# shield_mega2.net
KiCad netlist of a schematic drawn in EAGLE
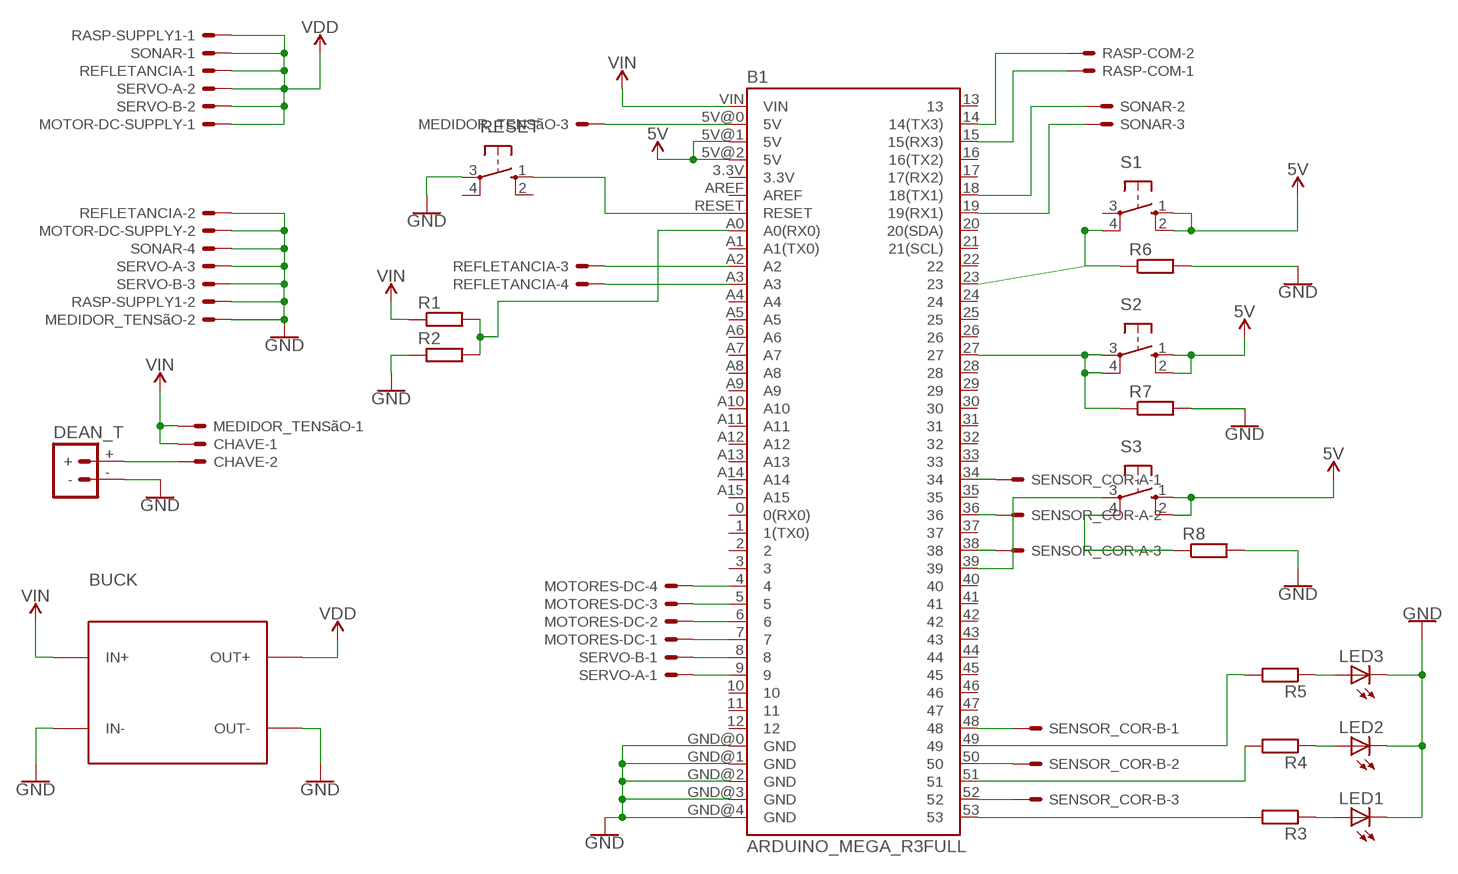
[diagram p0: schematic, sheet 1]

(export (version "E")
  (design (tool "Eeschema 10.0.6"))
  (components
    (comp (ref "B1")
      (value "ARDUINO_MEGA_R3FULL")
      (footprint "eagle-import:ARDUINO_MEGA")
      (libsource (lib "eagle-import") (part "ARDUINO_MEGA_R3FULL"))
    )
    (comp (ref "BUCK")
      (value "DC-DC-STEP-DOWN-LM2596")
      (footprint "eagle-import:DC-DC-STEP-DOWN-LM2596")
      (libsource (lib "eagle-import") (part "DC-DC-STEP-DOWN-LM2596"))
    )
    (comp (ref "CHAVE")
      (value "22-23-2021")
      (footprint "eagle-import:22-23-2021")
      (fields (field (name "MF") "MOLEX"))
      (libsource (lib "eagle-import") (part "22-23-2021"))
    )
    (comp (ref "DEAN_T")
      (value "BATTERY_CONN_DEANS")
      (footprint "eagle-import:DEANS")
      (libsource (lib "eagle-import") (part "BATTERY_CONN_DEANS"))
    )
    (comp (ref "LED1")
      (value "LED5MM")
      (footprint "eagle-import:LED5MM")
      (libsource (lib "eagle-import") (part "LED5MM"))
    )
    (comp (ref "LED2")
      (value "LED5MM")
      (footprint "eagle-import:LED5MM")
      (libsource (lib "eagle-import") (part "LED5MM"))
    )
    (comp (ref "LED3")
      (value "LED5MM")
      (footprint "eagle-import:LED5MM")
      (libsource (lib "eagle-import") (part "LED5MM"))
    )
    (comp (ref "MEDIDOR_TENSãO")
      (value "22-23-2031")
      (footprint "eagle-import:22-23-2031")
      (fields (field (name "MF") "MOLEX"))
      (libsource (lib "eagle-import") (part "22-23-2031"))
    )
    (comp (ref "MOTOR-DC-SUPPLY")
      (value "22-23-2021")
      (footprint "eagle-import:22-23-2021")
      (fields (field (name "MF") "MOLEX"))
      (libsource (lib "eagle-import") (part "22-23-2021"))
    )
    (comp (ref "MOTORES-DC")
      (value "22-23-2041")
      (footprint "eagle-import:22-23-2041")
      (fields (field (name "MF") "MOLEX"))
      (libsource (lib "eagle-import") (part "22-23-2041"))
    )
    (comp (ref "R1")
      (value "R-EU_0207/12")
      (footprint "eagle-import:0207_12")
      (libsource (lib "eagle-import") (part "R-EU_0207/12"))
    )
    (comp (ref "R2")
      (value "R-EU_0207/12")
      (footprint "eagle-import:0207_12")
      (libsource (lib "eagle-import") (part "R-EU_0207/12"))
    )
    (comp (ref "R3")
      (value "R-EU_0207/7")
      (footprint "eagle-import:0207_7")
      (libsource (lib "eagle-import") (part "R-EU_0207/7"))
    )
    (comp (ref "R4")
      (value "R-EU_0207/7")
      (footprint "eagle-import:0207_7")
      (libsource (lib "eagle-import") (part "R-EU_0207/7"))
    )
    (comp (ref "R5")
      (value "R-EU_0207/7")
      (footprint "eagle-import:0207_7")
      (libsource (lib "eagle-import") (part "R-EU_0207/7"))
    )
    (comp (ref "R6")
      (value "R-EU_0204/7")
      (footprint "eagle-import:0204_7")
      (libsource (lib "eagle-import") (part "R-EU_0204/7"))
    )
    (comp (ref "R7")
      (value "R-EU_0204/7")
      (footprint "eagle-import:0204_7")
      (libsource (lib "eagle-import") (part "R-EU_0204/7"))
    )
    (comp (ref "R8")
      (value "R-EU_0204/7")
      (footprint "eagle-import:0204_7")
      (libsource (lib "eagle-import") (part "R-EU_0204/7"))
    )
    (comp (ref "RASP-COM")
      (value "22-23-2021")
      (footprint "eagle-import:22-23-2021")
      (fields (field (name "MF") "MOLEX"))
      (libsource (lib "eagle-import") (part "22-23-2021"))
    )
    (comp (ref "RASP-SUPPLY1")
      (value "22-23-2021")
      (footprint "eagle-import:22-23-2021")
      (fields (field (name "MF") "MOLEX"))
      (libsource (lib "eagle-import") (part "22-23-2021"))
    )
    (comp (ref "REFLETANCIA")
      (value "22-23-2041")
      (footprint "eagle-import:22-23-2041")
      (fields (field (name "MF") "MOLEX"))
      (libsource (lib "eagle-import") (part "22-23-2041"))
    )
    (comp (ref "RESET")
      (value "10-XX")
      (footprint "eagle-import:B3F-10XX")
      (fields (field (name "MPN") "B3F-1000"))
      (libsource (lib "eagle-import") (part "10-XX"))
    )
    (comp (ref "S1")
      (value "10-XX")
      (footprint "eagle-import:B3F-10XX")
      (fields (field (name "MPN") "B3F-1000"))
      (libsource (lib "eagle-import") (part "10-XX"))
    )
    (comp (ref "S2")
      (value "10-XX")
      (footprint "eagle-import:B3F-10XX")
      (fields (field (name "MPN") "B3F-1000"))
      (libsource (lib "eagle-import") (part "10-XX"))
    )
    (comp (ref "S3")
      (value "10-XX")
      (footprint "eagle-import:B3F-10XX")
      (fields (field (name "MPN") "B3F-1000"))
      (libsource (lib "eagle-import") (part "10-XX"))
    )
    (comp (ref "SENSOR_COR-A")
      (value "22-23-2031")
      (footprint "eagle-import:22-23-2031")
      (fields (field (name "MF") "MOLEX"))
      (libsource (lib "eagle-import") (part "22-23-2031"))
    )
    (comp (ref "SENSOR_COR-B")
      (value "22-23-2031")
      (footprint "eagle-import:22-23-2031")
      (fields (field (name "MF") "MOLEX"))
      (libsource (lib "eagle-import") (part "22-23-2031"))
    )
    (comp (ref "SERVO-A")
      (value "22-23-2031")
      (footprint "eagle-import:22-23-2031")
      (fields (field (name "MF") "MOLEX"))
      (libsource (lib "eagle-import") (part "22-23-2031"))
    )
    (comp (ref "SERVO-B")
      (value "22-23-2031")
      (footprint "eagle-import:22-23-2031")
      (fields (field (name "MF") "MOLEX"))
      (libsource (lib "eagle-import") (part "22-23-2031"))
    )
    (comp (ref "SONAR")
      (value "22-23-2041")
      (footprint "eagle-import:22-23-2041")
      (fields (field (name "MF") "MOLEX"))
      (libsource (lib "eagle-import") (part "22-23-2041"))
    )
  )
  (nets
    (net (code "1") (name "5V") (class "Default")
      (node (ref "B1") (pin "5V@1") (pinfunction "5V_5V@1") (pintype "bidirectional"))
      (node (ref "B1") (pin "5V@2") (pinfunction "5V_5V@2") (pintype "bidirectional"))
      (node (ref "S1") (pin "1") (pinfunction "S_1") (pintype "passive"))
      (node (ref "S1") (pin "2") (pinfunction "S1_2") (pintype "passive"))
      (node (ref "S2") (pin "1") (pinfunction "S_1") (pintype "passive"))
      (node (ref "S2") (pin "2") (pinfunction "S1_2") (pintype "passive"))
      (node (ref "S3") (pin "1") (pinfunction "S_1") (pintype "passive"))
      (node (ref "S3") (pin "2") (pinfunction "S1_2") (pintype "passive"))
    )
    (net (code "2") (name "GND") (class "Default")
      (node (ref "B1") (pin "GND@0") (pinfunction "GND_GND@0") (pintype "bidirectional"))
      (node (ref "B1") (pin "GND@1") (pinfunction "GND_GND@1") (pintype "bidirectional"))
      (node (ref "B1") (pin "GND@2") (pinfunction "GND_GND@2") (pintype "bidirectional"))
      (node (ref "B1") (pin "GND@3") (pinfunction "GND_GND@3") (pintype "bidirectional"))
      (node (ref "B1") (pin "GND@4") (pinfunction "GND_GND@4") (pintype "bidirectional"))
      (node (ref "BUCK") (pin "IN-") (pinfunction "IN-_IN-") (pintype "bidirectional"))
      (node (ref "BUCK") (pin "OUT-") (pinfunction "OUT-_OUT-") (pintype "bidirectional"))
      (node (ref "DEAN_T") (pin "-") (pinfunction "-_-") (pintype "passive"))
      (node (ref "LED1") (pin "K") (pinfunction "C_K") (pintype "passive"))
      (node (ref "LED2") (pin "K") (pinfunction "C_K") (pintype "passive"))
      (node (ref "LED3") (pin "K") (pinfunction "C_K") (pintype "passive"))
      (node (ref "MEDIDOR_TENSãO") (pin "2") (pinfunction "S_2") (pintype "passive"))
      (node (ref "MOTOR-DC-SUPPLY") (pin "2") (pinfunction "S_2") (pintype "passive"))
      (node (ref "R2") (pin "1") (pinfunction "1_1") (pintype "passive"))
      (node (ref "R6") (pin "2") (pinfunction "2_2") (pintype "passive"))
      (node (ref "R7") (pin "2") (pinfunction "2_2") (pintype "passive"))
      (node (ref "R8") (pin "2") (pinfunction "2_2") (pintype "passive"))
      (node (ref "RASP-SUPPLY1") (pin "2") (pinfunction "S_2") (pintype "passive"))
      (node (ref "REFLETANCIA") (pin "2") (pinfunction "S_2") (pintype "passive"))
      (node (ref "RESET") (pin "3") (pinfunction "P_3") (pintype "passive"))
      (node (ref "SERVO-A") (pin "3") (pinfunction "S_3") (pintype "passive"))
      (node (ref "SERVO-B") (pin "3") (pinfunction "S_3") (pintype "passive"))
      (node (ref "SONAR") (pin "4") (pinfunction "S_4") (pintype "passive"))
    )
    (net (code "3") (name "Net-(B1-14(TX3))") (class "Default")
      (node (ref "B1") (pin "14") (pinfunction "14(TX3)_14") (pintype "bidirectional"))
      (node (ref "RASP-COM") (pin "2") (pinfunction "S_2") (pintype "passive"))
    )
    (net (code "4") (name "Net-(B1-15(RX3))") (class "Default")
      (node (ref "B1") (pin "15") (pinfunction "15(RX3)_15") (pintype "bidirectional"))
      (node (ref "RASP-COM") (pin "1") (pinfunction "S_1") (pintype "passive"))
    )
    (net (code "5") (name "Net-(B1-18(TX1))") (class "Default")
      (node (ref "B1") (pin "18") (pinfunction "18(TX1)_18") (pintype "bidirectional"))
      (node (ref "SONAR") (pin "2") (pinfunction "S_2") (pintype "passive"))
    )
    (net (code "6") (name "Net-(B1-19(RX1))") (class "Default")
      (node (ref "B1") (pin "19") (pinfunction "19(RX1)_19") (pintype "bidirectional"))
      (node (ref "SONAR") (pin "3") (pinfunction "S_3") (pintype "passive"))
    )
    (net (code "7") (name "Net-(B1-A0(RX0))") (class "Default")
      (node (ref "B1") (pin "A0") (pinfunction "A0(RX0)_A0") (pintype "bidirectional"))
      (node (ref "R1") (pin "2") (pinfunction "2_2") (pintype "passive"))
      (node (ref "R2") (pin "2") (pinfunction "2_2") (pintype "passive"))
    )
    (net (code "8") (name "Net-(B1-Pad49)") (class "Default")
      (node (ref "B1") (pin "49") (pinfunction "49_49") (pintype "bidirectional"))
      (node (ref "R5") (pin "2") (pinfunction "2_2") (pintype "passive"))
    )
    (net (code "9") (name "Net-(B1-Pad51)") (class "Default")
      (node (ref "B1") (pin "51") (pinfunction "51_51") (pintype "bidirectional"))
      (node (ref "R4") (pin "2") (pinfunction "2_2") (pintype "passive"))
    )
    (net (code "10") (name "Net-(B1-Pad53)") (class "Default")
      (node (ref "B1") (pin "53") (pinfunction "53_53") (pintype "bidirectional"))
      (node (ref "R3") (pin "2") (pinfunction "2_2") (pintype "passive"))
    )
    (net (code "11") (name "Net-(CHAVEB-S)") (class "Default")
      (node (ref "CHAVE") (pin "2") (pinfunction "S_2") (pintype "passive"))
      (node (ref "DEAN_T") (pin "+") (pinfunction "+_+") (pintype "passive"))
    )
    (net (code "12") (name "Net-(LED1-PadA)") (class "Default")
      (node (ref "LED1") (pin "A") (pinfunction "A_A") (pintype "passive"))
      (node (ref "R3") (pin "1") (pinfunction "1_1") (pintype "passive"))
    )
    (net (code "13") (name "Net-(LED2-PadA)") (class "Default")
      (node (ref "LED2") (pin "A") (pinfunction "A_A") (pintype "passive"))
      (node (ref "R4") (pin "1") (pinfunction "1_1") (pintype "passive"))
    )
    (net (code "14") (name "Net-(LED3-PadA)") (class "Default")
      (node (ref "LED3") (pin "A") (pinfunction "A_A") (pintype "passive"))
      (node (ref "R5") (pin "1") (pinfunction "1_1") (pintype "passive"))
    )
    (net (code "15") (name "Net-(MEDIDOR_TENSãOC-S)") (class "Default")
      (node (ref "B1") (pin "5V@0") (pinfunction "5V_5V@0") (pintype "bidirectional"))
      (node (ref "MEDIDOR_TENSãO") (pin "3") (pinfunction "S_3") (pintype "passive"))
    )
    (net (code "16") (name "Net-(MOTORES-DCA-S)") (class "Default")
      (node (ref "B1") (pin "7") (pinfunction "7_7") (pintype "bidirectional"))
      (node (ref "MOTORES-DC") (pin "1") (pinfunction "S_1") (pintype "passive"))
    )
    (net (code "17") (name "Net-(MOTORES-DCB-S)") (class "Default")
      (node (ref "B1") (pin "6") (pinfunction "6_6") (pintype "bidirectional"))
      (node (ref "MOTORES-DC") (pin "2") (pinfunction "S_2") (pintype "passive"))
    )
    (net (code "18") (name "Net-(MOTORES-DCC-S)") (class "Default")
      (node (ref "B1") (pin "5") (pinfunction "5_5") (pintype "bidirectional"))
      (node (ref "MOTORES-DC") (pin "3") (pinfunction "S_3") (pintype "passive"))
    )
    (net (code "19") (name "Net-(MOTORES-DCD-S)") (class "Default")
      (node (ref "B1") (pin "4") (pinfunction "4_4") (pintype "bidirectional"))
      (node (ref "MOTORES-DC") (pin "4") (pinfunction "S_4") (pintype "passive"))
    )
    (net (code "20") (name "Net-(REFLETANCIAC-S)") (class "Default")
      (node (ref "B1") (pin "A2") (pinfunction "A2_A2") (pintype "bidirectional"))
      (node (ref "REFLETANCIA") (pin "3") (pinfunction "S_3") (pintype "passive"))
    )
    (net (code "21") (name "Net-(REFLETANCIAD-S)") (class "Default")
      (node (ref "B1") (pin "A3") (pinfunction "A3_A3") (pintype "bidirectional"))
      (node (ref "REFLETANCIA") (pin "4") (pinfunction "S_4") (pintype "passive"))
    )
    (net (code "22") (name "Net-(RESET-S)") (class "Default")
      (node (ref "B1") (pin "RESET") (pinfunction "RESET_RESET") (pintype "bidirectional"))
      (node (ref "RESET") (pin "1") (pinfunction "S_1") (pintype "passive"))
    )
    (net (code "23") (name "Net-(S1-P1)") (class "Default")
      (node (ref "B1") (pin "23") (pinfunction "23_23") (pintype "bidirectional"))
      (node (ref "R6") (pin "1") (pinfunction "1_1") (pintype "passive"))
      (node (ref "S1") (pin "4") (pinfunction "P1_4") (pintype "passive"))
    )
    (net (code "24") (name "Net-(S2-P)") (class "Default")
      (node (ref "B1") (pin "27") (pinfunction "27_27") (pintype "bidirectional"))
      (node (ref "R7") (pin "1") (pinfunction "1_1") (pintype "passive"))
      (node (ref "S2") (pin "3") (pinfunction "P_3") (pintype "passive"))
      (node (ref "S2") (pin "4") (pinfunction "P1_4") (pintype "passive"))
    )
    (net (code "25") (name "Net-(S3-P)") (class "Default")
      (node (ref "B1") (pin "39") (pinfunction "39_39") (pintype "bidirectional"))
      (node (ref "S3") (pin "3") (pinfunction "P_3") (pintype "passive"))
    )
    (net (code "26") (name "Net-(S3-P1)") (class "Default")
      (node (ref "R8") (pin "1") (pinfunction "1_1") (pintype "passive"))
      (node (ref "S3") (pin "4") (pinfunction "P1_4") (pintype "passive"))
    )
    (net (code "27") (name "Net-(SENSOR_COR-AA-S)") (class "Default")
      (node (ref "B1") (pin "34") (pinfunction "34_34") (pintype "bidirectional"))
      (node (ref "SENSOR_COR-A") (pin "1") (pinfunction "S_1") (pintype "passive"))
    )
    (net (code "28") (name "Net-(SENSOR_COR-AB-S)") (class "Default")
      (node (ref "B1") (pin "36") (pinfunction "36_36") (pintype "bidirectional"))
      (node (ref "SENSOR_COR-A") (pin "2") (pinfunction "S_2") (pintype "passive"))
    )
    (net (code "29") (name "Net-(SENSOR_COR-AC-S)") (class "Default")
      (node (ref "B1") (pin "38") (pinfunction "38_38") (pintype "bidirectional"))
      (node (ref "SENSOR_COR-A") (pin "3") (pinfunction "S_3") (pintype "passive"))
    )
    (net (code "30") (name "Net-(SENSOR_COR-BA-S)") (class "Default")
      (node (ref "B1") (pin "48") (pinfunction "48_48") (pintype "bidirectional"))
      (node (ref "SENSOR_COR-B") (pin "1") (pinfunction "S_1") (pintype "passive"))
    )
    (net (code "31") (name "Net-(SENSOR_COR-BB-S)") (class "Default")
      (node (ref "B1") (pin "50") (pinfunction "50_50") (pintype "bidirectional"))
      (node (ref "SENSOR_COR-B") (pin "2") (pinfunction "S_2") (pintype "passive"))
    )
    (net (code "32") (name "Net-(SENSOR_COR-BC-S)") (class "Default")
      (node (ref "B1") (pin "52") (pinfunction "52_52") (pintype "bidirectional"))
      (node (ref "SENSOR_COR-B") (pin "3") (pinfunction "S_3") (pintype "passive"))
    )
    (net (code "33") (name "Net-(SERVO-AA-S)") (class "Default")
      (node (ref "B1") (pin "9") (pinfunction "9_9") (pintype "bidirectional"))
      (node (ref "SERVO-A") (pin "1") (pinfunction "S_1") (pintype "passive"))
    )
    (net (code "34") (name "Net-(SERVO-BA-S)") (class "Default")
      (node (ref "B1") (pin "8") (pinfunction "8_8") (pintype "bidirectional"))
      (node (ref "SERVO-B") (pin "1") (pinfunction "S_1") (pintype "passive"))
    )
    (net (code "35") (name "VDD") (class "Default")
      (node (ref "BUCK") (pin "OUT+") (pinfunction "OUT+_OUT+") (pintype "bidirectional"))
      (node (ref "MOTOR-DC-SUPPLY") (pin "1") (pinfunction "S_1") (pintype "passive"))
      (node (ref "RASP-SUPPLY1") (pin "1") (pinfunction "S_1") (pintype "passive"))
      (node (ref "REFLETANCIA") (pin "1") (pinfunction "S_1") (pintype "passive"))
      (node (ref "SERVO-A") (pin "2") (pinfunction "S_2") (pintype "passive"))
      (node (ref "SERVO-B") (pin "2") (pinfunction "S_2") (pintype "passive"))
      (node (ref "SONAR") (pin "1") (pinfunction "S_1") (pintype "passive"))
    )
    (net (code "36") (name "VIN") (class "Default")
      (node (ref "B1") (pin "VIN") (pinfunction "VIN_VIN") (pintype "bidirectional"))
      (node (ref "BUCK") (pin "IN+") (pinfunction "IN+_IN+") (pintype "bidirectional"))
      (node (ref "CHAVE") (pin "1") (pinfunction "S_1") (pintype "passive"))
      (node (ref "MEDIDOR_TENSãO") (pin "1") (pinfunction "S_1") (pintype "passive"))
      (node (ref "R1") (pin "1") (pinfunction "1_1") (pintype "passive"))
    )
    (net (code "37") (name "unconnected-(B1-0(RX0)-Pad0)") (class "Default")
      (node (ref "B1") (pin "0") (pinfunction "0(RX0)_0") (pintype "bidirectional"))
    )
    (net (code "38") (name "unconnected-(B1-1(TX0)-Pad1)") (class "Default")
      (node (ref "B1") (pin "1") (pinfunction "1(TX0)_1") (pintype "bidirectional"))
    )
    (net (code "39") (name "unconnected-(B1-16(TX2)-Pad16)") (class "Default")
      (node (ref "B1") (pin "16") (pinfunction "16(TX2)_16") (pintype "bidirectional"))
    )
    (net (code "40") (name "unconnected-(B1-17(RX2)-Pad17)") (class "Default")
      (node (ref "B1") (pin "17") (pinfunction "17(RX2)_17") (pintype "bidirectional"))
    )
    (net (code "41") (name "unconnected-(B1-20(SDA)-Pad20)") (class "Default")
      (node (ref "B1") (pin "20") (pinfunction "20(SDA)_20") (pintype "bidirectional"))
    )
    (net (code "42") (name "unconnected-(B1-21(SCL)-Pad21)") (class "Default")
      (node (ref "B1") (pin "21") (pinfunction "21(SCL)_21") (pintype "bidirectional"))
    )
    (net (code "43") (name "unconnected-(B1-A1(TX0)-PadA1)") (class "Default")
      (node (ref "B1") (pin "A1") (pinfunction "A1(TX0)_A1") (pintype "bidirectional"))
    )
    (net (code "44") (name "unconnected-(B1-Pad2)") (class "Default")
      (node (ref "B1") (pin "2") (pinfunction "2_2") (pintype "bidirectional"))
    )
    (net (code "45") (name "unconnected-(B1-Pad3)") (class "Default")
      (node (ref "B1") (pin "3") (pinfunction "3_3") (pintype "bidirectional"))
    )
    (net (code "46") (name "unconnected-(B1-Pad3.3V)") (class "Default")
      (node (ref "B1") (pin "3.3V") (pinfunction "3.3V_3.3V") (pintype "bidirectional"))
    )
    (net (code "47") (name "unconnected-(B1-Pad10)") (class "Default")
      (node (ref "B1") (pin "10") (pinfunction "10_10") (pintype "bidirectional"))
    )
    (net (code "48") (name "unconnected-(B1-Pad11)") (class "Default")
      (node (ref "B1") (pin "11") (pinfunction "11_11") (pintype "bidirectional"))
    )
    (net (code "49") (name "unconnected-(B1-Pad12)") (class "Default")
      (node (ref "B1") (pin "12") (pinfunction "12_12") (pintype "bidirectional"))
    )
    (net (code "50") (name "unconnected-(B1-Pad13)") (class "Default")
      (node (ref "B1") (pin "13") (pinfunction "13_13") (pintype "bidirectional"))
    )
    (net (code "51") (name "unconnected-(B1-Pad22)") (class "Default")
      (node (ref "B1") (pin "22") (pinfunction "22_22") (pintype "bidirectional"))
    )
    (net (code "52") (name "unconnected-(B1-Pad24)") (class "Default")
      (node (ref "B1") (pin "24") (pinfunction "24_24") (pintype "bidirectional"))
    )
    (net (code "53") (name "unconnected-(B1-Pad25)") (class "Default")
      (node (ref "B1") (pin "25") (pinfunction "25_25") (pintype "bidirectional"))
    )
    (net (code "54") (name "unconnected-(B1-Pad26)") (class "Default")
      (node (ref "B1") (pin "26") (pinfunction "26_26") (pintype "bidirectional"))
    )
    (net (code "55") (name "unconnected-(B1-Pad28)") (class "Default")
      (node (ref "B1") (pin "28") (pinfunction "28_28") (pintype "bidirectional"))
    )
    (net (code "56") (name "unconnected-(B1-Pad29)") (class "Default")
      (node (ref "B1") (pin "29") (pinfunction "29_29") (pintype "bidirectional"))
    )
    (net (code "57") (name "unconnected-(B1-Pad30)") (class "Default")
      (node (ref "B1") (pin "30") (pinfunction "30_30") (pintype "bidirectional"))
    )
    (net (code "58") (name "unconnected-(B1-Pad31)") (class "Default")
      (node (ref "B1") (pin "31") (pinfunction "31_31") (pintype "bidirectional"))
    )
    (net (code "59") (name "unconnected-(B1-Pad32)") (class "Default")
      (node (ref "B1") (pin "32") (pinfunction "32_32") (pintype "bidirectional"))
    )
    (net (code "60") (name "unconnected-(B1-Pad33)") (class "Default")
      (node (ref "B1") (pin "33") (pinfunction "33_33") (pintype "bidirectional"))
    )
    (net (code "61") (name "unconnected-(B1-Pad35)") (class "Default")
      (node (ref "B1") (pin "35") (pinfunction "35_35") (pintype "bidirectional"))
    )
    (net (code "62") (name "unconnected-(B1-Pad37)") (class "Default")
      (node (ref "B1") (pin "37") (pinfunction "37_37") (pintype "bidirectional"))
    )
    (net (code "63") (name "unconnected-(B1-Pad40)") (class "Default")
      (node (ref "B1") (pin "40") (pinfunction "40_40") (pintype "bidirectional"))
    )
    (net (code "64") (name "unconnected-(B1-Pad41)") (class "Default")
      (node (ref "B1") (pin "41") (pinfunction "41_41") (pintype "bidirectional"))
    )
    (net (code "65") (name "unconnected-(B1-Pad42)") (class "Default")
      (node (ref "B1") (pin "42") (pinfunction "42_42") (pintype "bidirectional"))
    )
    (net (code "66") (name "unconnected-(B1-Pad43)") (class "Default")
      (node (ref "B1") (pin "43") (pinfunction "43_43") (pintype "bidirectional"))
    )
    (net (code "67") (name "unconnected-(B1-Pad44)") (class "Default")
      (node (ref "B1") (pin "44") (pinfunction "44_44") (pintype "bidirectional"))
    )
    (net (code "68") (name "unconnected-(B1-Pad45)") (class "Default")
      (node (ref "B1") (pin "45") (pinfunction "45_45") (pintype "bidirectional"))
    )
    (net (code "69") (name "unconnected-(B1-Pad46)") (class "Default")
      (node (ref "B1") (pin "46") (pinfunction "46_46") (pintype "bidirectional"))
    )
    (net (code "70") (name "unconnected-(B1-Pad47)") (class "Default")
      (node (ref "B1") (pin "47") (pinfunction "47_47") (pintype "bidirectional"))
    )
    (net (code "71") (name "unconnected-(B1-PadA4)") (class "Default")
      (node (ref "B1") (pin "A4") (pinfunction "A4_A4") (pintype "bidirectional"))
    )
    (net (code "72") (name "unconnected-(B1-PadA5)") (class "Default")
      (node (ref "B1") (pin "A5") (pinfunction "A5_A5") (pintype "bidirectional"))
    )
    (net (code "73") (name "unconnected-(B1-PadA6)") (class "Default")
      (node (ref "B1") (pin "A6") (pinfunction "A6_A6") (pintype "bidirectional"))
    )
    (net (code "74") (name "unconnected-(B1-PadA7)") (class "Default")
      (node (ref "B1") (pin "A7") (pinfunction "A7_A7") (pintype "bidirectional"))
    )
    (net (code "75") (name "unconnected-(B1-PadA8)") (class "Default")
      (node (ref "B1") (pin "A8") (pinfunction "A8_A8") (pintype "bidirectional"))
    )
    (net (code "76") (name "unconnected-(B1-PadA9)") (class "Default")
      (node (ref "B1") (pin "A9") (pinfunction "A9_A9") (pintype "bidirectional"))
    )
    (net (code "77") (name "unconnected-(B1-PadA10)") (class "Default")
      (node (ref "B1") (pin "A10") (pinfunction "A10_A10") (pintype "bidirectional"))
    )
    (net (code "78") (name "unconnected-(B1-PadA11)") (class "Default")
      (node (ref "B1") (pin "A11") (pinfunction "A11_A11") (pintype "bidirectional"))
    )
    (net (code "79") (name "unconnected-(B1-PadA12)") (class "Default")
      (node (ref "B1") (pin "A12") (pinfunction "A12_A12") (pintype "bidirectional"))
    )
    (net (code "80") (name "unconnected-(B1-PadA13)") (class "Default")
      (node (ref "B1") (pin "A13") (pinfunction "A13_A13") (pintype "bidirectional"))
    )
    (net (code "81") (name "unconnected-(B1-PadA14)") (class "Default")
      (node (ref "B1") (pin "A14") (pinfunction "A14_A14") (pintype "bidirectional"))
    )
    (net (code "82") (name "unconnected-(B1-PadA15)") (class "Default")
      (node (ref "B1") (pin "A15") (pinfunction "A15_A15") (pintype "bidirectional"))
    )
    (net (code "83") (name "unconnected-(B1-PadAREF)") (class "Default")
      (node (ref "B1") (pin "AREF") (pinfunction "AREF_AREF") (pintype "bidirectional"))
    )
    (net (code "84") (name "unconnected-(RESET-P1-Pad4)") (class "Default")
      (node (ref "RESET") (pin "4") (pinfunction "P1_4") (pintype "passive"))
    )
    (net (code "85") (name "unconnected-(RESET-S1-Pad2)") (class "Default")
      (node (ref "RESET") (pin "2") (pinfunction "S1_2") (pintype "passive"))
    )
    (net (code "86") (name "unconnected-(S1-P-Pad3)") (class "Default")
      (node (ref "S1") (pin "3") (pinfunction "P_3") (pintype "passive"))
    )
  )
)
